# GSM_Power_Switch.net
KiCad netlist of a schematic drawn in Altium Designer
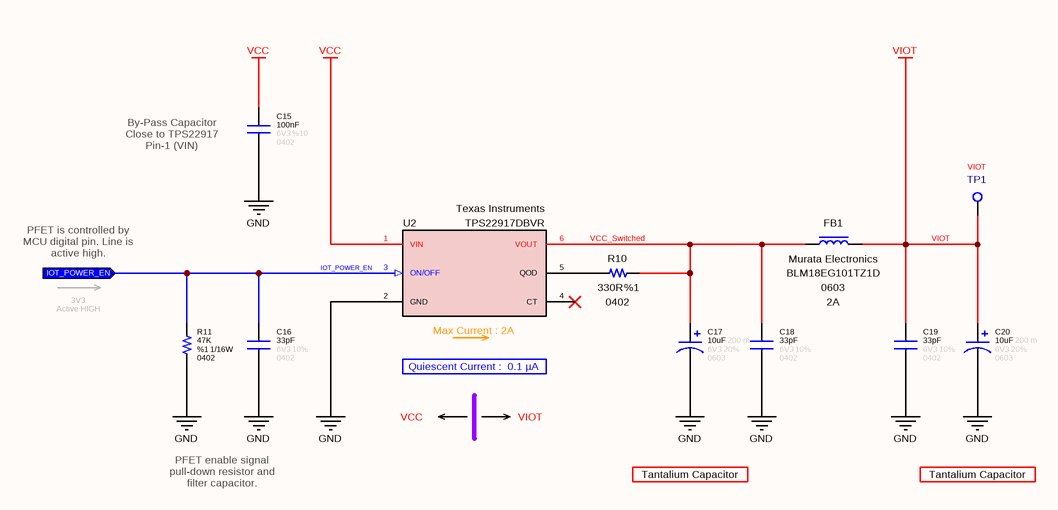
[diagram p0: GSM Power Switch.SchDoc]

(export (version "E")
  (design (tool "Eeschema 10.0.6"))
  (components
    (comp (ref "C15")
      (value "100nF")
      (footprint "CAPACITOR_0402")
      (description "Capacitor - 100nF [0402-6V3] (Ceramic)")
      (fields
        (field (name "MANUFACTURER PART NUMBER") "04026D104KAT4A")
        (field (name "TOLERANCE") "%10")
        (field (name "VOLTAGE") "6V3")
        (field (name "CASE") "0402")
        (field (name "Comment") "Capacitor - 100nF [0402] (Ceramic)")
      )
      (libsource (lib "P101DA_Library") (part "Capacitor - 100nF [0402-6V3]"))
    )
    (comp (ref "C16")
      (value "33pF")
      (footprint "CAPACITOR_0402")
      (description "Capacitor - 33pF [0402] (Ceramic)")
      (fields
        (field (name "MANUFACTURER PART NUMBER") "C0402C330J9RACAUTO")
        (field (name "TOLERANCE") "10%")
        (field (name "CASE") "0402")
        (field (name "VOLTAGE") "6V3")
      )
      (libsource (lib "P101DA_Library") (part "Capacitor - 33pF [0402-6V3]"))
    )
    (comp (ref "C17")
      (value "10uF")
      (footprint "CAPACITOR_0603_Tantalum")
      (description "Capacitor - 10uF [0603] (Tantalium)")
      (fields
        (field (name "MANUFACTURER PART NUMBER") "F380J106MMAAH3")
        (field (name "ESR") "200 m")
        (field (name "TOLERANCE") "20%")
        (field (name "CASE") "0603")
        (field (name "VOLTAGE") "6V3")
        (field (name "Comment") "Capacitor - 10uF [0603] (Tantalum)")
      )
      (libsource (lib "P101DA_Library") (part "Capacitor - 10uF [0603-6V3] (Tantalium)"))
    )
    (comp (ref "C18")
      (value "33pF")
      (footprint "CAPACITOR_0402")
      (description "Capacitor - 33pF [0402] (Ceramic)")
      (fields
        (field (name "MANUFACTURER PART NUMBER") "C0402C330J9RACAUTO")
        (field (name "TOLERANCE") "10%")
        (field (name "CASE") "0402")
        (field (name "VOLTAGE") "6V3")
      )
      (libsource (lib "P101DA_Library") (part "Capacitor - 33pF [0402-6V3]"))
    )
    (comp (ref "C19")
      (value "33pF")
      (footprint "CAPACITOR_0402")
      (description "Capacitor - 33pF [0402] (Ceramic)")
      (fields
        (field (name "MANUFACTURER PART NUMBER") "C0402C330J9RACAUTO")
        (field (name "TOLERANCE") "10%")
        (field (name "CASE") "0402")
        (field (name "VOLTAGE") "6V3")
      )
      (libsource (lib "P101DA_Library") (part "Capacitor - 33pF [0402-6V3]"))
    )
    (comp (ref "C20")
      (value "10uF")
      (footprint "CAPACITOR_0603_Tantalum")
      (description "Capacitor - 10uF [0603] (Tantalium)")
      (fields
        (field (name "MANUFACTURER PART NUMBER") "F380J106MMAAH3")
        (field (name "ESR") "200 m")
        (field (name "TOLERANCE") "20%")
        (field (name "CASE") "0603")
        (field (name "VOLTAGE") "6V3")
        (field (name "Comment") "Capacitor - 10uF [0603] (Tantalum)")
      )
      (libsource (lib "P101DA_Library") (part "Capacitor - 10uF [0603-6V3] (Tantalium)"))
    )
    (comp (ref "FB1")
      (value "~")
      (footprint "INDUCTOR_0603")
      (description "Ferrite Beads 0603 100ohms 2000mA Auto Infotainment")
      (fields
        (field (name "TOLERANCE") "25%")
        (field (name "CASE") "0603")
        (field (name "MAXIMUM DC CURRENT") "2A")
        (field (name "MANUFACTURER PART NUMBER") "BLM18EG101TZ1D")
        (field (name "MANUFACTURER NAME") "Murata Electronics")
      )
      (libsource (lib "P101DA_Library") (part "Ferrite Bead [SMD]"))
    )
    (comp (ref "R10")
      (value "330R")
      (footprint "RESISTOR_0402")
      (description "Thick Film Resistors - SMD 1/16 W 330 Ohm 1%")
      (fields
        (field (name "TOLERANCE") "%1")
        (field (name "CASE") "0402")
        (field (name "MANUFACTURER PART NUMBER") "CRCW0402330RFKED")
      )
      (libsource (lib "P101DA_Library") (part "330R"))
    )
    (comp (ref "R11")
      (value "47K")
      (footprint "RESISTOR_0402")
      (description "Thick Film Resistors - SMD 1/16 W 47 KOhm 1%")
      (fields
        (field (name "MANUFACTURER PART NUMBER") "CRCW040247K0FKED")
        (field (name "TOLERANCE") "%1")
        (field (name "CASE") "0402")
        (field (name "POWER") "1/16W")
        (field (name "Comment") "47K - 0402 - %1 - 1/16W")
      )
      (libsource (lib "P101DA_Library") (part "Resistor - 47K [0402]"))
    )
    (comp (ref "TP1")
      (value "~")
      (footprint "Test_Point")
      (description "Test Point")
      (fields (field (name "NAME") "VIOT"))
      (libsource (lib "P101DA_Library") (part "Test Point"))
    )
    (comp (ref "U2")
      (value "Power Switch")
      (footprint "SOT-23-6")
      (description "Power Switch MosFet")
      (fields
        (field (name "MANUFACTURER PART NUMBER") "TPS22917DBVR")
        (field (name "MANUFACTURER NAME") "Texas Instruments")
      )
      (libsource (lib "P101DA_Library") (part "IC - TPS22917"))
    )
  )
  (nets
    (net (code "1") (name "/IOT_POWER_EN") (class "Default")
      (node (ref "C16") (pin "2") (pinfunction "2_2") (pintype "passive"))
      (node (ref "R11") (pin "2") (pinfunction "2_2") (pintype "passive"))
      (node (ref "U2") (pin "3") (pinfunction "ON/OFF_3") (pintype "input"))
    )
    (net (code "2") (name "/VCC_Switched") (class "Default")
      (node (ref "C17") (pin "1") (pinfunction "1_1") (pintype "passive"))
      (node (ref "C18") (pin "2") (pinfunction "2_2") (pintype "passive"))
      (node (ref "FB1") (pin "1") (pinfunction "1_1") (pintype "passive"))
      (node (ref "R10") (pin "1") (pinfunction "1_1") (pintype "passive"))
      (node (ref "U2") (pin "6") (pinfunction "VOUT_6") (pintype "power_in"))
    )
    (net (code "3") (name "GND") (class "Default")
      (node (ref "C15") (pin "1") (pinfunction "1_1") (pintype "passive"))
      (node (ref "C16") (pin "1") (pinfunction "1_1") (pintype "passive"))
      (node (ref "C17") (pin "2") (pinfunction "2_2") (pintype "passive"))
      (node (ref "C18") (pin "1") (pinfunction "1_1") (pintype "passive"))
      (node (ref "C19") (pin "1") (pinfunction "1_1") (pintype "passive"))
      (node (ref "C20") (pin "2") (pinfunction "2_2") (pintype "passive"))
      (node (ref "R11") (pin "1") (pinfunction "1_1") (pintype "passive"))
      (node (ref "U2") (pin "2") (pinfunction "GND_2") (pintype "power_in"))
    )
    (net (code "4") (name "Net-(U2-QOD)") (class "Default")
      (node (ref "R10") (pin "2") (pinfunction "2_2") (pintype "passive"))
      (node (ref "U2") (pin "5") (pinfunction "QOD_5") (pintype "power_in"))
    )
    (net (code "5") (name "VCC") (class "Default")
      (node (ref "C15") (pin "2") (pinfunction "2_2") (pintype "passive"))
      (node (ref "U2") (pin "1") (pinfunction "VIN_1") (pintype "power_in"))
    )
    (net (code "6") (name "VIOT") (class "Default")
      (node (ref "C19") (pin "2") (pinfunction "2_2") (pintype "passive"))
      (node (ref "C20") (pin "1") (pinfunction "1_1") (pintype "passive"))
      (node (ref "FB1") (pin "2") (pinfunction "2_2") (pintype "passive"))
      (node (ref "TP1") (pin "1") (pinfunction "1_1") (pintype "passive"))
    )
    (net (code "7") (name "unconnected-(U2-CT-Pad4)") (class "Default")
      (node (ref "U2") (pin "4") (pinfunction "CT_4") (pintype "power_in+no_connect"))
    )
  )
)
